# S3_Connectors.net
KiCad netlist of a schematic drawn in Altium Designer
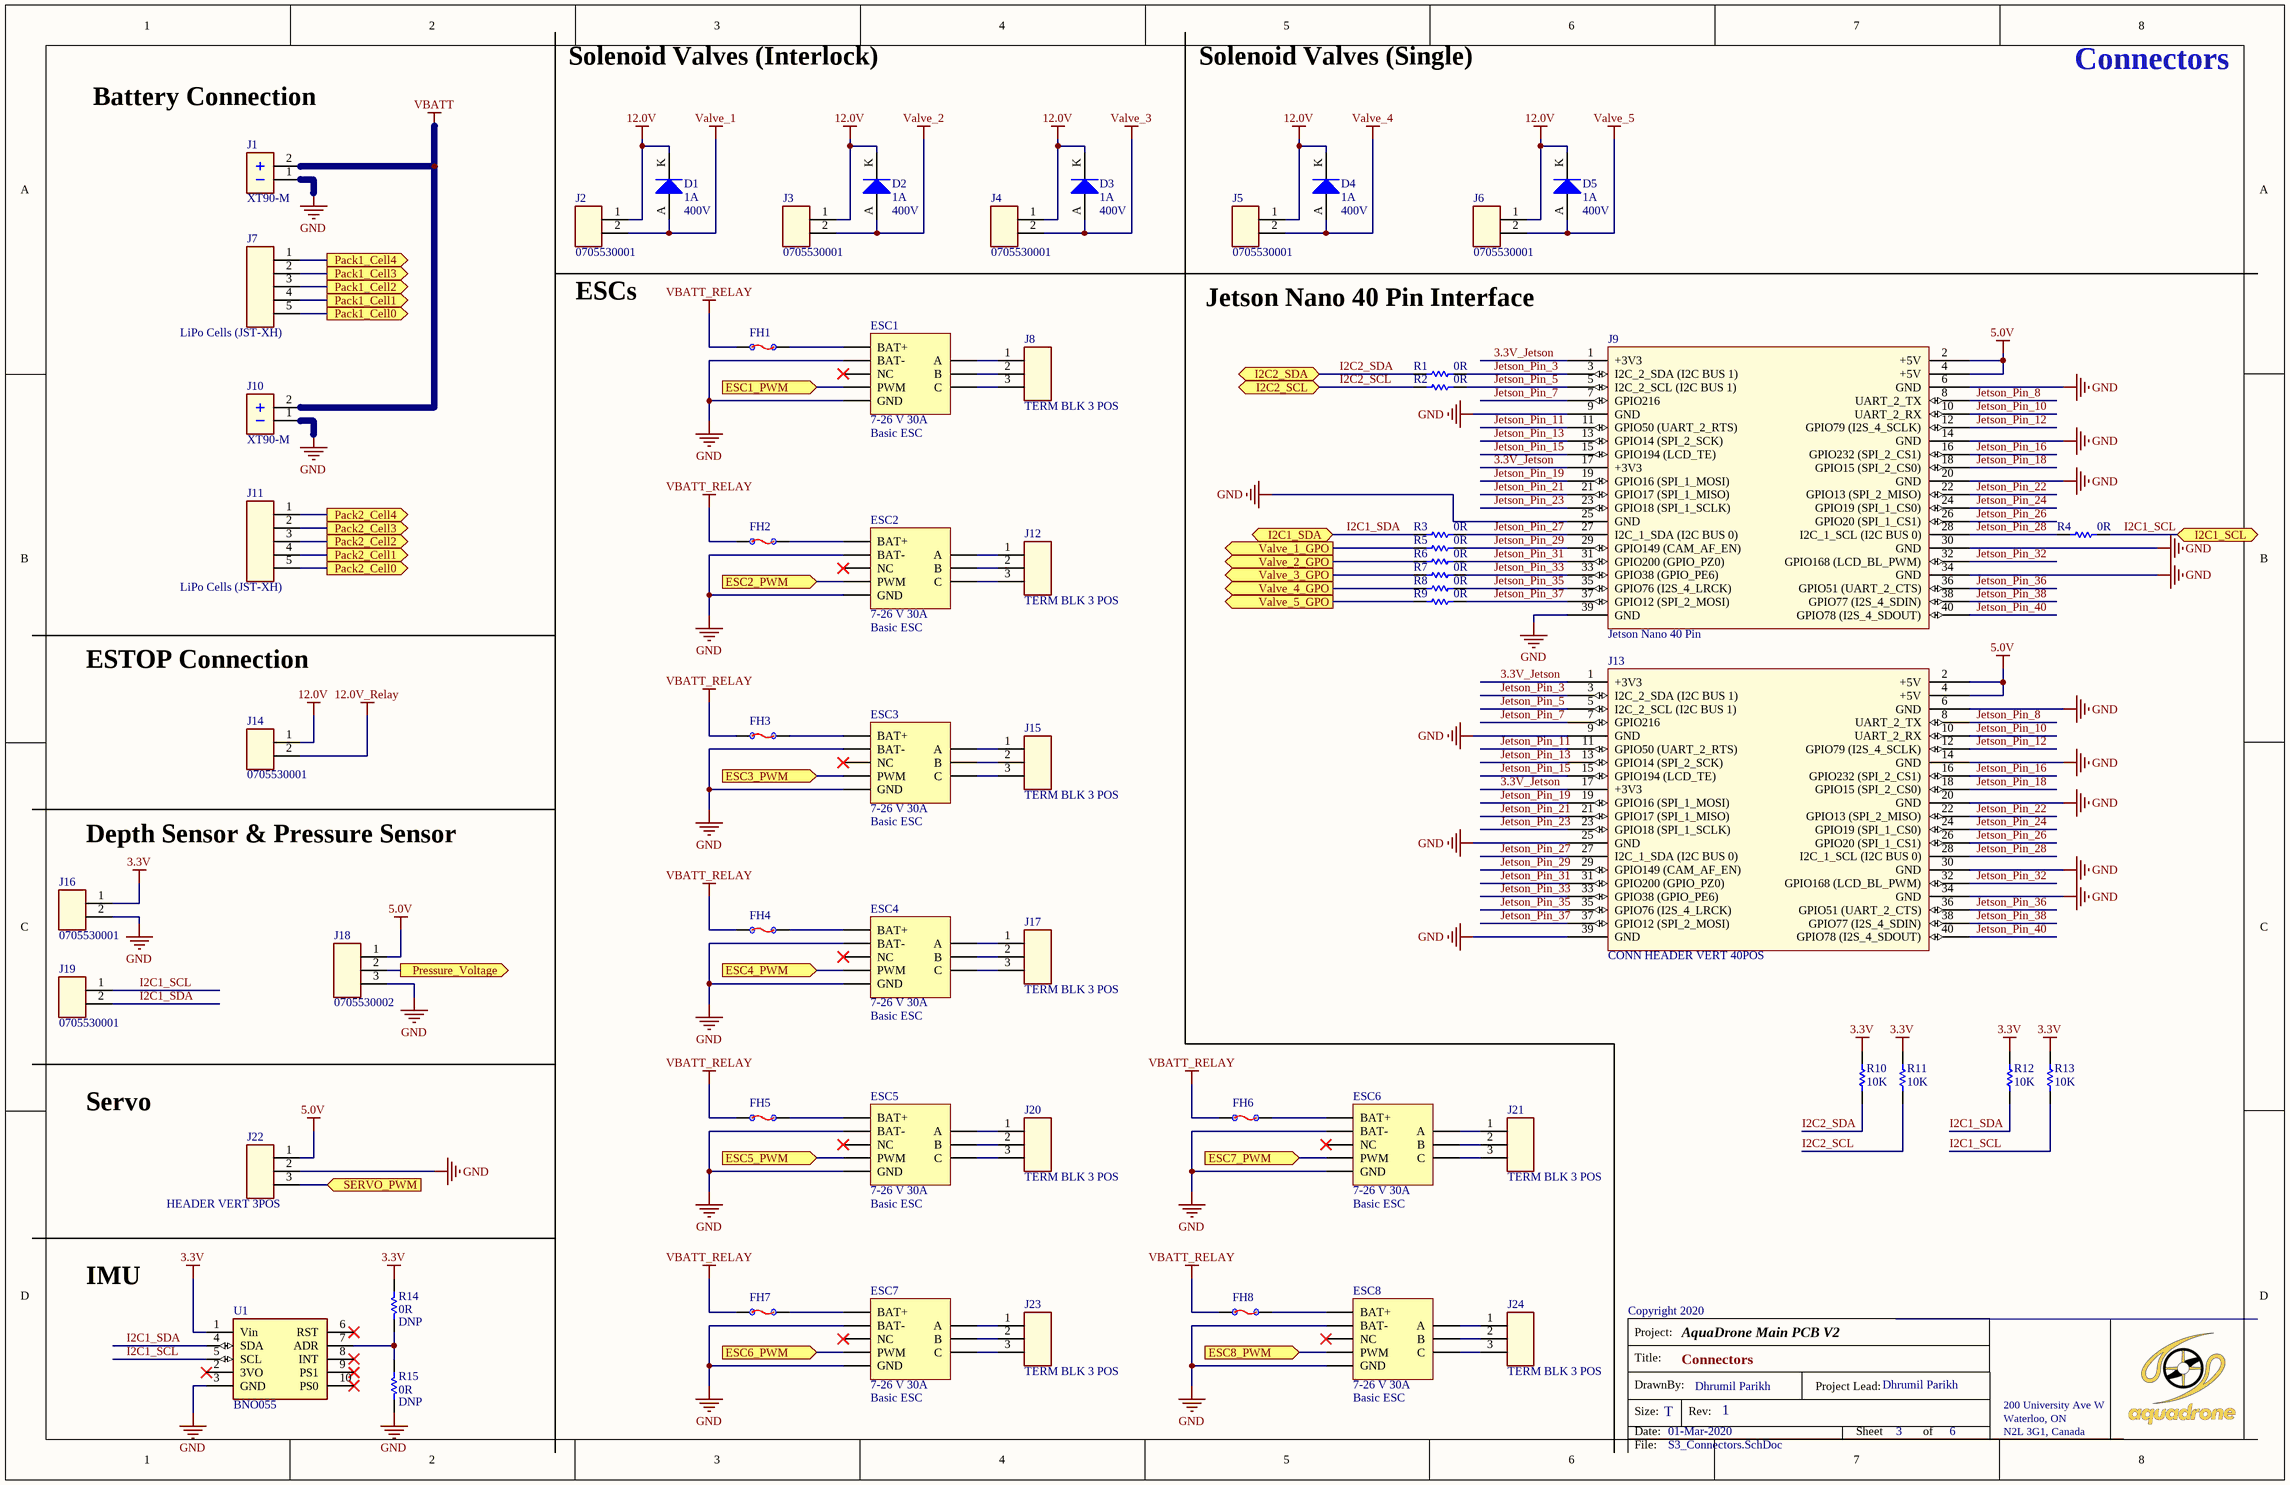
[diagram p0: S3_Connectors.SchDoc]

(export (version "E")
  (design (tool "Eeschema 10.0.6"))
  (components
    (comp (ref "D1")
      (value "DIODE GEN PURP 400V 1A SMA")
      (footprint "DIOM5226X295N")
      (fields
        (field (name "MFG") "SMC Diode Solutions")
        (field (name "MFG_PART_NO") "S1GTR")
        (field (name "CURRENT") "1A")
        (field (name "VR") "400V")
      )
      (libsource (lib "AquaDrone") (part "DIODE GEN PURP 400V 1A SMA"))
    )
    (comp (ref "D2")
      (value "DIODE GEN PURP 400V 1A SMA")
      (footprint "DIOM5226X295N")
      (fields
        (field (name "MFG") "SMC Diode Solutions")
        (field (name "MFG_PART_NO") "S1GTR")
        (field (name "CURRENT") "1A")
        (field (name "VR") "400V")
      )
      (libsource (lib "AquaDrone") (part "DIODE GEN PURP 400V 1A SMA"))
    )
    (comp (ref "D3")
      (value "DIODE GEN PURP 400V 1A SMA")
      (footprint "DIOM5226X295N")
      (fields
        (field (name "MFG") "SMC Diode Solutions")
        (field (name "MFG_PART_NO") "S1GTR")
        (field (name "CURRENT") "1A")
        (field (name "VR") "400V")
      )
      (libsource (lib "AquaDrone") (part "DIODE GEN PURP 400V 1A SMA"))
    )
    (comp (ref "D4")
      (value "DIODE GEN PURP 400V 1A SMA")
      (footprint "DIOM5226X295N")
      (fields
        (field (name "MFG") "SMC Diode Solutions")
        (field (name "MFG_PART_NO") "S1GTR")
        (field (name "CURRENT") "1A")
        (field (name "VR") "400V")
      )
      (libsource (lib "AquaDrone") (part "DIODE GEN PURP 400V 1A SMA"))
    )
    (comp (ref "D5")
      (value "DIODE GEN PURP 400V 1A SMA")
      (footprint "DIOM5226X295N")
      (fields
        (field (name "MFG") "SMC Diode Solutions")
        (field (name "MFG_PART_NO") "S1GTR")
        (field (name "CURRENT") "1A")
        (field (name "VR") "400V")
      )
      (libsource (lib "AquaDrone") (part "DIODE GEN PURP 400V 1A SMA"))
    )
    (comp (ref "ESC1")
      (value "Basic ESC")
      (footprint "ESC BR")
      (fields
        (field (name "MFG") "Blue Robotics")
        (field (name "MFG_PART_NO") "BESC30-R3")
        (field (name "VOLTAGE") "7-26 V 30A")
      )
      (libsource (lib "AquaDrone") (part "Basic ESC"))
    )
    (comp (ref "ESC2")
      (value "Basic ESC")
      (footprint "ESC BR")
      (fields
        (field (name "MFG") "Blue Robotics")
        (field (name "MFG_PART_NO") "BESC30-R3")
        (field (name "VOLTAGE") "7-26 V 30A")
      )
      (libsource (lib "AquaDrone") (part "Basic ESC"))
    )
    (comp (ref "ESC3")
      (value "Basic ESC")
      (footprint "ESC BR")
      (fields
        (field (name "MFG") "Blue Robotics")
        (field (name "MFG_PART_NO") "BESC30-R3")
        (field (name "VOLTAGE") "7-26 V 30A")
      )
      (libsource (lib "AquaDrone") (part "Basic ESC"))
    )
    (comp (ref "ESC4")
      (value "Basic ESC")
      (footprint "ESC BR")
      (fields
        (field (name "MFG") "Blue Robotics")
        (field (name "MFG_PART_NO") "BESC30-R3")
        (field (name "VOLTAGE") "7-26 V 30A")
      )
      (libsource (lib "AquaDrone") (part "Basic ESC"))
    )
    (comp (ref "ESC5")
      (value "Basic ESC")
      (footprint "ESC BR")
      (fields
        (field (name "MFG") "Blue Robotics")
        (field (name "MFG_PART_NO") "BESC30-R3")
        (field (name "VOLTAGE") "7-26 V 30A")
      )
      (libsource (lib "AquaDrone") (part "Basic ESC"))
    )
    (comp (ref "ESC6")
      (value "Basic ESC")
      (footprint "ESC BR")
      (fields
        (field (name "MFG") "Blue Robotics")
        (field (name "MFG_PART_NO") "BESC30-R3")
        (field (name "VOLTAGE") "7-26 V 30A")
      )
      (libsource (lib "AquaDrone") (part "Basic ESC"))
    )
    (comp (ref "ESC7")
      (value "Basic ESC")
      (footprint "ESC BR")
      (fields
        (field (name "MFG") "Blue Robotics")
        (field (name "MFG_PART_NO") "BESC30-R3")
        (field (name "VOLTAGE") "7-26 V 30A")
      )
      (libsource (lib "AquaDrone") (part "Basic ESC"))
    )
    (comp (ref "ESC8")
      (value "Basic ESC")
      (footprint "ESC BR")
      (fields
        (field (name "MFG") "Blue Robotics")
        (field (name "MFG_PART_NO") "BESC30-R3")
        (field (name "VOLTAGE") "7-26 V 30A")
      )
      (libsource (lib "AquaDrone") (part "Basic ESC"))
    )
    (comp (ref "FH1")
      (value "FUSE BLOK CARTRIDGE 600V 16A PCB")
      (footprint "FUSE-HOLDER(5X20)")
      (fields
        (field (name "MFG") "Schurter Inc.")
        (field (name "MFG_PART_NO") "0031.8231")
        (field (name "VOLTAGE") "600V")
      )
      (libsource (lib "AquaDrone") (part "FUSE BLOK CARTRIDGE 600V 16A PCB"))
    )
    (comp (ref "FH2")
      (value "FUSE BLOK CARTRIDGE 600V 16A PCB")
      (footprint "FUSE-HOLDER(5X20)")
      (fields
        (field (name "MFG") "Schurter Inc.")
        (field (name "MFG_PART_NO") "0031.8231")
        (field (name "VOLTAGE") "600V")
      )
      (libsource (lib "AquaDrone") (part "FUSE BLOK CARTRIDGE 600V 16A PCB"))
    )
    (comp (ref "FH3")
      (value "FUSE BLOK CARTRIDGE 600V 16A PCB")
      (footprint "FUSE-HOLDER(5X20)")
      (fields
        (field (name "MFG") "Schurter Inc.")
        (field (name "MFG_PART_NO") "0031.8231")
        (field (name "VOLTAGE") "600V")
      )
      (libsource (lib "AquaDrone") (part "FUSE BLOK CARTRIDGE 600V 16A PCB"))
    )
    (comp (ref "FH4")
      (value "FUSE BLOK CARTRIDGE 600V 16A PCB")
      (footprint "FUSE-HOLDER(5X20)")
      (fields
        (field (name "MFG") "Schurter Inc.")
        (field (name "MFG_PART_NO") "0031.8231")
        (field (name "VOLTAGE") "600V")
      )
      (libsource (lib "AquaDrone") (part "FUSE BLOK CARTRIDGE 600V 16A PCB"))
    )
    (comp (ref "FH5")
      (value "FUSE BLOK CARTRIDGE 600V 16A PCB")
      (footprint "FUSE-HOLDER(5X20)")
      (fields
        (field (name "MFG") "Schurter Inc.")
        (field (name "MFG_PART_NO") "0031.8231")
        (field (name "VOLTAGE") "600V")
      )
      (libsource (lib "AquaDrone") (part "FUSE BLOK CARTRIDGE 600V 16A PCB"))
    )
    (comp (ref "FH6")
      (value "FUSE BLOK CARTRIDGE 600V 16A PCB")
      (footprint "FUSE-HOLDER(5X20)")
      (fields
        (field (name "MFG") "Schurter Inc.")
        (field (name "MFG_PART_NO") "0031.8231")
        (field (name "VOLTAGE") "600V")
      )
      (libsource (lib "AquaDrone") (part "FUSE BLOK CARTRIDGE 600V 16A PCB"))
    )
    (comp (ref "FH7")
      (value "FUSE BLOK CARTRIDGE 600V 16A PCB")
      (footprint "FUSE-HOLDER(5X20)")
      (fields
        (field (name "MFG") "Schurter Inc.")
        (field (name "MFG_PART_NO") "0031.8231")
        (field (name "VOLTAGE") "600V")
      )
      (libsource (lib "AquaDrone") (part "FUSE BLOK CARTRIDGE 600V 16A PCB"))
    )
    (comp (ref "FH8")
      (value "FUSE BLOK CARTRIDGE 600V 16A PCB")
      (footprint "FUSE-HOLDER(5X20)")
      (fields
        (field (name "MFG") "Schurter Inc.")
        (field (name "MFG_PART_NO") "0031.8231")
        (field (name "VOLTAGE") "600V")
      )
      (libsource (lib "AquaDrone") (part "FUSE BLOK CARTRIDGE 600V 16A PCB"))
    )
    (comp (ref "J1")
      (value "XT90-M")
      (footprint "XT90")
      (description "CONN XT90 MALE")
      (fields (field (name "MFG") "DFRobot") (field (name "MFG_PART_NO") "FIT0588"))
      (libsource (lib "AquaDrone") (part "CONN XT90 MALE"))
    )
    (comp (ref "J2")
      (value "0705530001")
      (footprint "SHDRRA2W109P0_254_1X2_762X1359X699P")
      (description "CONN HEADER R/A 2POS 2.54MM")
      (fields (field (name "MFG") "Molex"))
      (libsource (lib "AquaDrone") (part "CONN HEADER R/A 2POS 2.54MM"))
    )
    (comp (ref "J3")
      (value "0705530001")
      (footprint "SHDRRA2W109P0_254_1X2_762X1359X699P")
      (description "CONN HEADER R/A 2POS 2.54MM")
      (fields (field (name "MFG") "Molex"))
      (libsource (lib "AquaDrone") (part "CONN HEADER R/A 2POS 2.54MM"))
    )
    (comp (ref "J4")
      (value "0705530001")
      (footprint "SHDRRA2W109P0_254_1X2_762X1359X699P")
      (description "CONN HEADER R/A 2POS 2.54MM")
      (fields (field (name "MFG") "Molex"))
      (libsource (lib "AquaDrone") (part "CONN HEADER R/A 2POS 2.54MM"))
    )
    (comp (ref "J5")
      (value "0705530001")
      (footprint "SHDRRA2W109P0_254_1X2_762X1359X699P")
      (description "CONN HEADER R/A 2POS 2.54MM")
      (fields (field (name "MFG") "Molex"))
      (libsource (lib "AquaDrone") (part "CONN HEADER R/A 2POS 2.54MM"))
    )
    (comp (ref "J6")
      (value "0705530001")
      (footprint "SHDRRA2W109P0_254_1X2_762X1359X699P")
      (description "CONN HEADER R/A 2POS 2.54MM")
      (fields (field (name "MFG") "Molex"))
      (libsource (lib "AquaDrone") (part "CONN HEADER R/A 2POS 2.54MM"))
    )
    (comp (ref "J7")
      (value "LiPo Cells (JST-XH)")
      (footprint "SHDR5W64P0X250_1X5_1490X1150X610P")
      (description "CONN HEADER R/A 5POS 2.5MM")
      (fields (field (name "MFG") "JST Sales America Inc.") (field (name "MFG_PART_NO") "S5B-XH-A(LF)(SN)"))
      (libsource (lib "AquaDrone") (part "CONN HEADER R/A 5POS 2.5MM"))
    )
    (comp (ref "J8")
      (value "TERM BLK 3 POS")
      (footprint "SHDR3W100P0X254_1X3_808X650X1030P")
      (description "TERM BLK 3P SIDE ENT 2.54MM PCB")
      (fields (field (name "MFG") "TE Connectivity") (field (name "MFG_PART_NO") "282834-3"))
      (libsource (lib "AquaDrone") (part "TERM BLK 3P SIDE ENT 2.54MM PCB"))
    )
    (comp (ref "J9")
      (value "Jetson Nano 40 Pin")
      (footprint "Jetson Nano")
      (description "Jetson Nano 40 Pin Interface")
      (fields (field (name "MFG") "Jetson") (field (name "MFG_PART_NO") "Nano"))
      (libsource (lib "AquaDrone") (part "Jetson Nano 40 Pin Interface"))
    )
    (comp (ref "J10")
      (value "XT90-M")
      (footprint "XT90")
      (description "CONN XT90 MALE")
      (fields (field (name "MFG") "DFRobot") (field (name "MFG_PART_NO") "FIT0588"))
      (libsource (lib "AquaDrone") (part "CONN XT90 MALE"))
    )
    (comp (ref "J11")
      (value "LiPo Cells (JST-XH)")
      (footprint "SHDR5W64P0X250_1X5_1490X1150X610P")
      (description "CONN HEADER R/A 5POS 2.5MM")
      (fields (field (name "MFG") "JST Sales America Inc.") (field (name "MFG_PART_NO") "S5B-XH-A(LF)(SN)"))
      (libsource (lib "AquaDrone") (part "CONN HEADER R/A 5POS 2.5MM"))
    )
    (comp (ref "J12")
      (value "TERM BLK 3 POS")
      (footprint "SHDR3W100P0X254_1X3_808X650X1030P")
      (description "TERM BLK 3P SIDE ENT 2.54MM PCB")
      (fields (field (name "MFG") "TE Connectivity") (field (name "MFG_PART_NO") "282834-3"))
      (libsource (lib "AquaDrone") (part "TERM BLK 3P SIDE ENT 2.54MM PCB"))
    )
    (comp (ref "J13")
      (value "CONN HEADER VERT 40POS")
      (footprint "67997-140HLF")
      (description "CONN HEADER VERT 40POS 2.54MM")
      (fields (field (name "MFG") "Amphenol") (field (name "MFG_PART_NO") "67997-140HLF"))
      (libsource (lib "AquaDrone") (part "CONN HEADER VERT 40POS 2.54MM"))
    )
    (comp (ref "J14")
      (value "0705530001")
      (footprint "SHDRRA2W109P0_254_1X2_762X1359X699P")
      (description "CONN HEADER R/A 2POS 2.54MM")
      (fields (field (name "MFG") "Molex"))
      (libsource (lib "AquaDrone") (part "CONN HEADER R/A 2POS 2.54MM"))
    )
    (comp (ref "J15")
      (value "TERM BLK 3 POS")
      (footprint "SHDR3W100P0X254_1X3_808X650X1030P")
      (description "TERM BLK 3P SIDE ENT 2.54MM PCB")
      (fields (field (name "MFG") "TE Connectivity") (field (name "MFG_PART_NO") "282834-3"))
      (libsource (lib "AquaDrone") (part "TERM BLK 3P SIDE ENT 2.54MM PCB"))
    )
    (comp (ref "J16")
      (value "0705530001")
      (footprint "SHDRRA2W109P0_254_1X2_762X1359X699P")
      (description "CONN HEADER R/A 2POS 2.54MM")
      (fields (field (name "MFG") "Molex"))
      (libsource (lib "AquaDrone") (part "CONN HEADER R/A 2POS 2.54MM"))
    )
    (comp (ref "J17")
      (value "TERM BLK 3 POS")
      (footprint "SHDR3W100P0X254_1X3_808X650X1030P")
      (description "TERM BLK 3P SIDE ENT 2.54MM PCB")
      (fields (field (name "MFG") "TE Connectivity") (field (name "MFG_PART_NO") "282834-3"))
      (libsource (lib "AquaDrone") (part "TERM BLK 3P SIDE ENT 2.54MM PCB"))
    )
    (comp (ref "J18")
      (value "0705530002")
      (footprint "SHDR3W89P0X254_1X3_1017X1359X699P")
      (description "CONN HEADER R/A 3POS 2.54MM")
      (fields (field (name "MFG") "Molex"))
      (libsource (lib "AquaDrone") (part "CONN HEADER R/A 3POS 2.54MM"))
    )
    (comp (ref "J19")
      (value "0705530001")
      (footprint "SHDRRA2W109P0_254_1X2_762X1359X699P")
      (description "CONN HEADER R/A 2POS 2.54MM")
      (fields (field (name "MFG") "Molex"))
      (libsource (lib "AquaDrone") (part "CONN HEADER R/A 2POS 2.54MM"))
    )
    (comp (ref "J20")
      (value "TERM BLK 3 POS")
      (footprint "SHDR3W100P0X254_1X3_808X650X1030P")
      (description "TERM BLK 3P SIDE ENT 2.54MM PCB")
      (fields (field (name "MFG") "TE Connectivity") (field (name "MFG_PART_NO") "282834-3"))
      (libsource (lib "AquaDrone") (part "TERM BLK 3P SIDE ENT 2.54MM PCB"))
    )
    (comp (ref "J21")
      (value "TERM BLK 3 POS")
      (footprint "SHDR3W100P0X254_1X3_808X650X1030P")
      (description "TERM BLK 3P SIDE ENT 2.54MM PCB")
      (fields (field (name "MFG") "TE Connectivity") (field (name "MFG_PART_NO") "282834-3"))
      (libsource (lib "AquaDrone") (part "TERM BLK 3P SIDE ENT 2.54MM PCB"))
    )
    (comp (ref "J22")
      (value "HEADER VERT 3POS")
      (footprint "RWMN:61300311121")
      (description "CONN HEADER VERT 3POS 2.54MM")
      (fields (field (name "MFG") "Wurth Electronics Inc.") (field (name "MFG_PART_NO") "61300311121"))
      (libsource (lib "AquaDrone") (part "CONN HEADER VERT 3POS 2.54MM"))
    )
    (comp (ref "J23")
      (value "TERM BLK 3 POS")
      (footprint "SHDR3W100P0X254_1X3_808X650X1030P")
      (description "TERM BLK 3P SIDE ENT 2.54MM PCB")
      (fields (field (name "MFG") "TE Connectivity") (field (name "MFG_PART_NO") "282834-3"))
      (libsource (lib "AquaDrone") (part "TERM BLK 3P SIDE ENT 2.54MM PCB"))
    )
    (comp (ref "J24")
      (value "TERM BLK 3 POS")
      (footprint "SHDR3W100P0X254_1X3_808X650X1030P")
      (description "TERM BLK 3P SIDE ENT 2.54MM PCB")
      (fields (field (name "MFG") "TE Connectivity") (field (name "MFG_PART_NO") "282834-3"))
      (libsource (lib "AquaDrone") (part "TERM BLK 3P SIDE ENT 2.54MM PCB"))
    )
    (comp (ref "R1")
      (value "0R")
      (footprint "RESC2012X07N")
      (description "RES SMD 0 OHM JUMPER 1/8W 0805")
      (fields (field (name "MFG") "Panasonic") (field (name "MFG_PART_NO") "ERJ-6GEY0R00V"))
      (libsource (lib "AquaDrone") (part "RES SMD 0 OHM JUMPER 1/8W 0805"))
    )
    (comp (ref "R2")
      (value "0R")
      (footprint "RESC2012X07N")
      (description "RES SMD 0 OHM JUMPER 1/8W 0805")
      (fields (field (name "MFG") "Panasonic") (field (name "MFG_PART_NO") "ERJ-6GEY0R00V"))
      (libsource (lib "AquaDrone") (part "RES SMD 0 OHM JUMPER 1/8W 0805"))
    )
    (comp (ref "R3")
      (value "0R")
      (footprint "RESC2012X07N")
      (description "RES SMD 0 OHM JUMPER 1/8W 0805")
      (fields (field (name "MFG") "Panasonic") (field (name "MFG_PART_NO") "ERJ-6GEY0R00V"))
      (libsource (lib "AquaDrone") (part "RES SMD 0 OHM JUMPER 1/8W 0805"))
    )
    (comp (ref "R4")
      (value "0R")
      (footprint "RESC2012X07N")
      (description "RES SMD 0 OHM JUMPER 1/8W 0805")
      (fields (field (name "MFG") "Panasonic") (field (name "MFG_PART_NO") "ERJ-6GEY0R00V"))
      (libsource (lib "AquaDrone") (part "RES SMD 0 OHM JUMPER 1/8W 0805"))
    )
    (comp (ref "R5")
      (value "0R")
      (footprint "RESC2012X07N")
      (description "RES SMD 0 OHM JUMPER 1/8W 0805")
      (fields (field (name "MFG") "Panasonic") (field (name "MFG_PART_NO") "ERJ-6GEY0R00V"))
      (libsource (lib "AquaDrone") (part "RES SMD 0 OHM JUMPER 1/8W 0805"))
    )
    (comp (ref "R6")
      (value "0R")
      (footprint "RESC2012X07N")
      (description "RES SMD 0 OHM JUMPER 1/8W 0805")
      (fields (field (name "MFG") "Panasonic") (field (name "MFG_PART_NO") "ERJ-6GEY0R00V"))
      (libsource (lib "AquaDrone") (part "RES SMD 0 OHM JUMPER 1/8W 0805"))
    )
    (comp (ref "R7")
      (value "0R")
      (footprint "RESC2012X07N")
      (description "RES SMD 0 OHM JUMPER 1/8W 0805")
      (fields (field (name "MFG") "Panasonic") (field (name "MFG_PART_NO") "ERJ-6GEY0R00V"))
      (libsource (lib "AquaDrone") (part "RES SMD 0 OHM JUMPER 1/8W 0805"))
    )
    (comp (ref "R8")
      (value "0R")
      (footprint "RESC2012X07N")
      (description "RES SMD 0 OHM JUMPER 1/8W 0805")
      (fields (field (name "MFG") "Panasonic") (field (name "MFG_PART_NO") "ERJ-6GEY0R00V"))
      (libsource (lib "AquaDrone") (part "RES SMD 0 OHM JUMPER 1/8W 0805"))
    )
    (comp (ref "R9")
      (value "0R")
      (footprint "RESC2012X07N")
      (description "RES SMD 0 OHM JUMPER 1/8W 0805")
      (fields (field (name "MFG") "Panasonic") (field (name "MFG_PART_NO") "ERJ-6GEY0R00V"))
      (libsource (lib "AquaDrone") (part "RES SMD 0 OHM JUMPER 1/8W 0805"))
    )
    (comp (ref "R10")
      (value "10K")
      (footprint "RESC1608X06N")
      (description "RES SMD 10K OHM 1% 1/10W 0603")
      (fields (field (name "MFG") "Vishay Dale") (field (name "MFG_PART_NO") "CRCW060310K0FKEA"))
      (libsource (lib "AquaDrone") (part "RES SMD 10K OHM 1% 1/10W 0603"))
    )
    (comp (ref "R11")
      (value "10K")
      (footprint "RESC1608X06N")
      (description "RES SMD 10K OHM 1% 1/10W 0603")
      (fields (field (name "MFG") "Vishay Dale") (field (name "MFG_PART_NO") "CRCW060310K0FKEA"))
      (libsource (lib "AquaDrone") (part "RES SMD 10K OHM 1% 1/10W 0603"))
    )
    (comp (ref "R12")
      (value "10K")
      (footprint "RESC1608X06N")
      (description "RES SMD 10K OHM 1% 1/10W 0603")
      (fields (field (name "MFG") "Vishay Dale") (field (name "MFG_PART_NO") "CRCW060310K0FKEA"))
      (libsource (lib "AquaDrone") (part "RES SMD 10K OHM 1% 1/10W 0603"))
    )
    (comp (ref "R13")
      (value "10K")
      (footprint "RESC1608X06N")
      (description "RES SMD 10K OHM 1% 1/10W 0603")
      (fields (field (name "MFG") "Vishay Dale") (field (name "MFG_PART_NO") "CRCW060310K0FKEA"))
      (libsource (lib "AquaDrone") (part "RES SMD 10K OHM 1% 1/10W 0603"))
    )
    (comp (ref "R14")
      (value "0R")
      (footprint "RESC2012X07N")
      (description "RES SMD 0 OHM JUMPER 1/8W 0805")
      (fields
        (field (name "MFG") "Panasonic")
        (field (name "NOSTUFF") "DNP")
        (field (name "MFG_PART_NO") "ERJ-6GEY0R00V")
      )
      (libsource (lib "AquaDrone") (part "RES SMD 0 OHM JUMPER 1/8W 0805"))
    )
    (comp (ref "R15")
      (value "0R")
      (footprint "RESC2012X07N")
      (description "RES SMD 0 OHM JUMPER 1/8W 0805")
      (fields
        (field (name "MFG") "Panasonic")
        (field (name "NOSTUFF") "DNP")
        (field (name "MFG_PART_NO") "ERJ-6GEY0R00V")
      )
      (libsource (lib "AquaDrone") (part "RES SMD 0 OHM JUMPER 1/8W 0805"))
    )
    (comp (ref "U1")
      (value "IC BNO055")
      (footprint "BNO055")
      (fields (field (name "MFG") "Adafruit Industries LLC") (field (name "MFG_PART_NO") "BNO055"))
      (libsource (lib "AquaDrone") (part "IC BNO055"))
    )
  )
  (nets
    (net (code "1") (name "/3.3V_Jetson") (class "Default")
      (node (ref "J13") (pin "1") (pinfunction "+3V3_1") (pintype "power_in"))
      (node (ref "J13") (pin "17") (pinfunction "+3V3_17") (pintype "power_in"))
      (node (ref "J9") (pin "1") (pinfunction "+3V3_1") (pintype "power_in"))
      (node (ref "J9") (pin "17") (pinfunction "+3V3_17") (pintype "power_in"))
    )
    (net (code "2") (name "/ESC1_PWM") (class "Default")
      (node (ref "ESC1") (pin "PWM") (pinfunction "PWM_PWM") (pintype "passive"))
    )
    (net (code "3") (name "/ESC2_PWM") (class "Default")
      (node (ref "ESC2") (pin "PWM") (pinfunction "PWM_PWM") (pintype "passive"))
    )
    (net (code "4") (name "/ESC3_PWM") (class "Default")
      (node (ref "ESC3") (pin "PWM") (pinfunction "PWM_PWM") (pintype "passive"))
    )
    (net (code "5") (name "/ESC4_PWM") (class "Default")
      (node (ref "ESC4") (pin "PWM") (pinfunction "PWM_PWM") (pintype "passive"))
    )
    (net (code "6") (name "/ESC5_PWM") (class "Default")
      (node (ref "ESC5") (pin "PWM") (pinfunction "PWM_PWM") (pintype "passive"))
    )
    (net (code "7") (name "/ESC6_PWM") (class "Default")
      (node (ref "ESC7") (pin "PWM") (pinfunction "PWM_PWM") (pintype "passive"))
    )
    (net (code "8") (name "/ESC7_PWM") (class "Default")
      (node (ref "ESC6") (pin "PWM") (pinfunction "PWM_PWM") (pintype "passive"))
    )
    (net (code "9") (name "/ESC8_PWM") (class "Default")
      (node (ref "ESC8") (pin "PWM") (pinfunction "PWM_PWM") (pintype "passive"))
    )
    (net (code "10") (name "/I2C1_SCL") (class "Default")
      (node (ref "J19") (pin "1") (pintype "passive"))
      (node (ref "R13") (pin "1") (pinfunction "1_1") (pintype "passive"))
      (node (ref "R4") (pin "2") (pinfunction "2_2") (pintype "passive"))
      (node (ref "U1") (pin "5") (pinfunction "SCL_5") (pintype "bidirectional"))
    )
    (net (code "11") (name "/I2C1_SDA") (class "Default")
      (node (ref "J19") (pin "2") (pintype "passive"))
      (node (ref "R12") (pin "1") (pinfunction "1_1") (pintype "passive"))
      (node (ref "R3") (pin "1") (pinfunction "1_1") (pintype "passive"))
      (node (ref "U1") (pin "4") (pinfunction "SDA_4") (pintype "bidirectional"))
    )
    (net (code "12") (name "/I2C2_SCL") (class "Default")
      (node (ref "R11") (pin "1") (pinfunction "1_1") (pintype "passive"))
      (node (ref "R2") (pin "1") (pinfunction "1_1") (pintype "passive"))
    )
    (net (code "13") (name "/I2C2_SDA") (class "Default")
      (node (ref "R1") (pin "1") (pinfunction "1_1") (pintype "passive"))
      (node (ref "R10") (pin "1") (pinfunction "1_1") (pintype "passive"))
    )
    (net (code "14") (name "/Jetson_Pin_3") (class "Default")
      (node (ref "J13") (pin "3") (pinfunction "I2C_2_SDA_(I2C_BUS_1)_3") (pintype "bidirectional"))
      (node (ref "J9") (pin "3") (pinfunction "I2C_2_SDA_(I2C_BUS_1)_3") (pintype "bidirectional"))
      (node (ref "R1") (pin "2") (pinfunction "2_2") (pintype "passive"))
    )
    (net (code "15") (name "/Jetson_Pin_5") (class "Default")
      (node (ref "J13") (pin "5") (pinfunction "I2C_2_SCL_(I2C_BUS_1)_5") (pintype "bidirectional"))
      (node (ref "J9") (pin "5") (pinfunction "I2C_2_SCL_(I2C_BUS_1)_5") (pintype "bidirectional"))
      (node (ref "R2") (pin "2") (pinfunction "2_2") (pintype "passive"))
    )
    (net (code "16") (name "/Jetson_Pin_7") (class "Default")
      (node (ref "J13") (pin "7") (pinfunction "GPIO216_7") (pintype "bidirectional"))
      (node (ref "J9") (pin "7") (pinfunction "GPIO216_7") (pintype "bidirectional"))
    )
    (net (code "17") (name "/Jetson_Pin_8") (class "Default")
      (node (ref "J13") (pin "8") (pinfunction "UART_2_TX_8") (pintype "bidirectional"))
      (node (ref "J9") (pin "8") (pinfunction "UART_2_TX_8") (pintype "bidirectional"))
    )
    (net (code "18") (name "/Jetson_Pin_10") (class "Default")
      (node (ref "J13") (pin "10") (pinfunction "UART_2_RX_10") (pintype "bidirectional"))
      (node (ref "J9") (pin "10") (pinfunction "UART_2_RX_10") (pintype "bidirectional"))
    )
    (net (code "19") (name "/Jetson_Pin_11") (class "Default")
      (node (ref "J13") (pin "11") (pinfunction "GPIO50_(UART_2_RTS)_11") (pintype "bidirectional"))
      (node (ref "J9") (pin "11") (pinfunction "GPIO50_(UART_2_RTS)_11") (pintype "bidirectional"))
    )
    (net (code "20") (name "/Jetson_Pin_12") (class "Default")
      (node (ref "J13") (pin "12") (pinfunction "GPIO79_(I2S_4_SCLK)_12") (pintype "bidirectional"))
      (node (ref "J9") (pin "12") (pinfunction "GPIO79_(I2S_4_SCLK)_12") (pintype "bidirectional"))
    )
    (net (code "21") (name "/Jetson_Pin_13") (class "Default")
      (node (ref "J13") (pin "13") (pinfunction "GPIO14_(SPI_2_SCK)_13") (pintype "bidirectional"))
      (node (ref "J9") (pin "13") (pinfunction "GPIO14_(SPI_2_SCK)_13") (pintype "bidirectional"))
    )
    (net (code "22") (name "/Jetson_Pin_15") (class "Default")
      (node (ref "J13") (pin "15") (pinfunction "GPIO194_(LCD_TE)_15") (pintype "bidirectional"))
      (node (ref "J9") (pin "15") (pinfunction "GPIO194_(LCD_TE)_15") (pintype "bidirectional"))
    )
    (net (code "23") (name "/Jetson_Pin_16") (class "Default")
      (node (ref "J13") (pin "16") (pinfunction "GPIO232_(SPI_2_CS1)_16") (pintype "bidirectional"))
      (node (ref "J9") (pin "16") (pinfunction "GPIO232_(SPI_2_CS1)_16") (pintype "bidirectional"))
    )
    (net (code "24") (name "/Jetson_Pin_18") (class "Default")
      (node (ref "J13") (pin "18") (pinfunction "GPIO15_(SPI_2_CS0)_18") (pintype "bidirectional"))
      (node (ref "J9") (pin "18") (pinfunction "GPIO15_(SPI_2_CS0)_18") (pintype "bidirectional"))
    )
    (net (code "25") (name "/Jetson_Pin_19") (class "Default")
      (node (ref "J13") (pin "19") (pinfunction "GPIO16_(SPI_1_MOSI)_19") (pintype "bidirectional"))
      (node (ref "J9") (pin "19") (pinfunction "GPIO16_(SPI_1_MOSI)_19") (pintype "bidirectional"))
    )
    (net (code "26") (name "/Jetson_Pin_21") (class "Default")
      (node (ref "J13") (pin "21") (pinfunction "GPIO17_(SPI_1_MISO)_21") (pintype "bidirectional"))
      (node (ref "J9") (pin "21") (pinfunction "GPIO17_(SPI_1_MISO)_21") (pintype "bidirectional"))
    )
    (net (code "27") (name "/Jetson_Pin_22") (class "Default")
      (node (ref "J13") (pin "22") (pinfunction "GPIO13_(SPI_2_MISO)_22") (pintype "bidirectional"))
      (node (ref "J9") (pin "22") (pinfunction "GPIO13_(SPI_2_MISO)_22") (pintype "bidirectional"))
    )
    (net (code "28") (name "/Jetson_Pin_23") (class "Default")
      (node (ref "J13") (pin "23") (pinfunction "GPIO18_(SPI_1_SCLK)_23") (pintype "bidirectional"))
      (node (ref "J9") (pin "23") (pinfunction "GPIO18_(SPI_1_SCLK)_23") (pintype "bidirectional"))
    )
    (net (code "29") (name "/Jetson_Pin_24") (class "Default")
      (node (ref "J13") (pin "24") (pinfunction "GPIO19_(SPI_1_CS0)_24") (pintype "bidirectional"))
      (node (ref "J9") (pin "24") (pinfunction "GPIO19_(SPI_1_CS0)_24") (pintype "bidirectional"))
    )
    (net (code "30") (name "/Jetson_Pin_26") (class "Default")
      (node (ref "J13") (pin "26") (pinfunction "GPIO20_(SPI_1_CS1)_26") (pintype "bidirectional"))
      (node (ref "J9") (pin "26") (pinfunction "GPIO20_(SPI_1_CS1)_26") (pintype "bidirectional"))
    )
    (net (code "31") (name "/Jetson_Pin_27") (class "Default")
      (node (ref "J13") (pin "27") (pinfunction "I2C_1_SDA_(I2C_BUS_0)_27") (pintype "passive"))
      (node (ref "J9") (pin "27") (pinfunction "I2C_1_SDA_(I2C_BUS_0)_27") (pintype "passive"))
      (node (ref "R3") (pin "2") (pinfunction "2_2") (pintype "passive"))
    )
    (net (code "32") (name "/Jetson_Pin_28") (class "Default")
      (node (ref "J13") (pin "28") (pinfunction "I2C_1_SCL_(I2C_BUS_0)_28") (pintype "passive"))
      (node (ref "J9") (pin "28") (pinfunction "I2C_1_SCL_(I2C_BUS_0)_28") (pintype "passive"))
      (node (ref "R4") (pin "1") (pinfunction "1_1") (pintype "passive"))
    )
    (net (code "33") (name "/Jetson_Pin_29") (class "Default")
      (node (ref "J13") (pin "29") (pinfunction "GPIO149_(CAM_AF_EN)_29") (pintype "bidirectional"))
      (node (ref "J9") (pin "29") (pinfunction "GPIO149_(CAM_AF_EN)_29") (pintype "bidirectional"))
      (node (ref "R5") (pin "2") (pinfunction "2_2") (pintype "passive"))
    )
    (net (code "34") (name "/Jetson_Pin_31") (class "Default")
      (node (ref "J13") (pin "31") (pinfunction "GPIO200_(GPIO_PZ0)_31") (pintype "bidirectional"))
      (node (ref "J9") (pin "31") (pinfunction "GPIO200_(GPIO_PZ0)_31") (pintype "bidirectional"))
      (node (ref "R6") (pin "2") (pinfunction "2_2") (pintype "passive"))
    )
    (net (code "35") (name "/Jetson_Pin_32") (class "Default")
      (node (ref "J13") (pin "32") (pinfunction "GPIO168_(LCD_BL_PWM)_32") (pintype "bidirectional"))
      (node (ref "J9") (pin "32") (pinfunction "GPIO168_(LCD_BL_PWM)_32") (pintype "bidirectional"))
    )
    (net (code "36") (name "/Jetson_Pin_33") (class "Default")
      (node (ref "J13") (pin "33") (pinfunction "GPIO38_(GPIO_PE6)_33") (pintype "bidirectional"))
      (node (ref "J9") (pin "33") (pinfunction "GPIO38_(GPIO_PE6)_33") (pintype "bidirectional"))
      (node (ref "R7") (pin "2") (pinfunction "2_2") (pintype "passive"))
    )
    (net (code "37") (name "/Jetson_Pin_35") (class "Default")
      (node (ref "J13") (pin "35") (pinfunction "GPIO76_(I2S_4_LRCK)_35") (pintype "bidirectional"))
      (node (ref "J9") (pin "35") (pinfunction "GPIO76_(I2S_4_LRCK)_35") (pintype "bidirectional"))
      (node (ref "R8") (pin "2") (pinfunction "2_2") (pintype "passive"))
    )
    (net (code "38") (name "/Jetson_Pin_36") (class "Default")
      (node (ref "J13") (pin "36") (pinfunction "GPIO51_(UART_2_CTS)_36") (pintype "bidirectional"))
      (node (ref "J9") (pin "36") (pinfunction "GPIO51_(UART_2_CTS)_36") (pintype "bidirectional"))
    )
    (net (code "39") (name "/Jetson_Pin_37") (class "Default")
      (node (ref "J13") (pin "37") (pinfunction "GPIO12_(SPI_2_MOSI)_37") (pintype "bidirectional"))
      (node (ref "J9") (pin "37") (pinfunction "GPIO12_(SPI_2_MOSI)_37") (pintype "bidirectional"))
      (node (ref "R9") (pin "2") (pinfunction "2_2") (pintype "passive"))
    )
    (net (code "40") (name "/Jetson_Pin_38") (class "Default")
      (node (ref "J13") (pin "38") (pinfunction "GPIO77_(I2S_4_SDIN)_38") (pintype "bidirectional"))
      (node (ref "J9") (pin "38") (pinfunction "GPIO77_(I2S_4_SDIN)_38") (pintype "bidirectional"))
    )
    (net (code "41") (name "/Jetson_Pin_40") (class "Default")
      (node (ref "J13") (pin "40") (pinfunction "GPIO78_(I2S_4_SDOUT)_40") (pintype "bidirectional"))
      (node (ref "J9") (pin "40") (pinfunction "GPIO78_(I2S_4_SDOUT)_40") (pintype "bidirectional"))
    )
    (net (code "42") (name "/Pack1_Cell0") (class "Default") (node (ref "J7") (pin "5") (pintype "passive")))
    (net (code "43") (name "/Pack1_Cell1") (class "Default") (node (ref "J7") (pin "4") (pintype "passive")))
    (net (code "44") (name "/Pack1_Cell2") (class "Default") (node (ref "J7") (pin "3") (pintype "passive")))
    (net (code "45") (name "/Pack1_Cell3") (class "Default") (node (ref "J7") (pin "2") (pintype "passive")))
    (net (code "46") (name "/Pack1_Cell4") (class "Default") (node (ref "J7") (pin "1") (pintype "passive")))
    (net (code "47") (name "/Pack2_Cell0") (class "Default") (node (ref "J11") (pin "5") (pintype "passive")))
    (net (code "48") (name "/Pack2_Cell1") (class "Default") (node (ref "J11") (pin "4") (pintype "passive")))
    (net (code "49") (name "/Pack2_Cell2") (class "Default") (node (ref "J11") (pin "3") (pintype "passive")))
    (net (code "50") (name "/Pack2_Cell3") (class "Default") (node (ref "J11") (pin "2") (pintype "passive")))
    (net (code "51") (name "/Pack2_Cell4") (class "Default") (node (ref "J11") (pin "1") (pintype "passive")))
    (net (code "52") (name "/Pressure_Voltage") (class "Default")
      (node (ref "J18") (pin "2") (pintype "passive"))
    )
    (net (code "53") (name "/SERVO_PWM") (class "Default") (node (ref "J22") (pin "3") (pintype "passive")))
    (net (code "54") (name "/Valve_1_GPO") (class "Default")
      (node (ref "R5") (pin "1") (pinfunction "1_1") (pintype "passive"))
    )
    (net (code "55") (name "/Valve_2_GPO") (class "Default")
      (node (ref "R6") (pin "1") (pinfunction "1_1") (pintype "passive"))
    )
    (net (code "56") (name "/Valve_3_GPO") (class "Default")
      (node (ref "R7") (pin "1") (pinfunction "1_1") (pintype "passive"))
    )
    (net (code "57") (name "/Valve_4_GPO") (class "Default")
      (node (ref "R8") (pin "1") (pinfunction "1_1") (pintype "passive"))
    )
    (net (code "58") (name "/Valve_5_GPO") (class "Default")
      (node (ref "R9") (pin "1") (pinfunction "1_1") (pintype "passive"))
    )
    (net (code "59") (name "3.3V") (class "Default")
      (node (ref "J16") (pin "1") (pintype "passive"))
      (node (ref "R10") (pin "2") (pinfunction "2_2") (pintype "passive"))
      (node (ref "R11") (pin "2") (pinfunction "2_2") (pintype "passive"))
      (node (ref "R12") (pin "2") (pinfunction "2_2") (pintype "passive"))
      (node (ref "R13") (pin "2") (pinfunction "2_2") (pintype "passive"))
      (node (ref "R14") (pin "1") (pinfunction "1_1") (pintype "passive"))
      (node (ref "U1") (pin "1") (pinfunction "Vin_1") (pintype "passive"))
    )
    (net (code "60") (name "5.0V") (class "Default")
      (node (ref "J13") (pin "2") (pinfunction "+5V_2") (pintype "power_in"))
      (node (ref "J13") (pin "4") (pinfunction "+5V_4") (pintype "power_in"))
      (node (ref "J18") (pin "1") (pintype "passive"))
      (node (ref "J22") (pin "1") (pintype "passive"))
      (node (ref "J9") (pin "2") (pinfunction "+5V_2") (pintype "power_in"))
      (node (ref "J9") (pin "4") (pinfunction "+5V_4") (pintype "power_in"))
    )
    (net (code "61") (name "12.0V") (class "Default")
      (node (ref "D1") (pin "K") (pinfunction "K_K") (pintype "passive"))
      (node (ref "D2") (pin "K") (pinfunction "K_K") (pintype "passive"))
      (node (ref "D3") (pin "K") (pinfunction "K_K") (pintype "passive"))
      (node (ref "D4") (pin "K") (pinfunction "K_K") (pintype "passive"))
      (node (ref "D5") (pin "K") (pinfunction "K_K") (pintype "passive"))
      (node (ref "J14") (pin "1") (pintype "passive"))
      (node (ref "J2") (pin "1") (pintype "passive"))
      (node (ref "J3") (pin "1") (pintype "passive"))
      (node (ref "J4") (pin "1") (pintype "passive"))
      (node (ref "J5") (pin "1") (pintype "passive"))
      (node (ref "J6") (pin "1") (pintype "passive"))
    )
    (net (code "62") (name "12.0V_Relay") (class "Default") (node (ref "J14") (pin "2") (pintype "passive")))
    (net (code "63") (name "GND") (class "Default")
      (node (ref "ESC1") (pin "BAT-") (pinfunction "BAT-_BAT-") (pintype "passive"))
      (node (ref "ESC1") (pin "GND") (pinfunction "GND_GND") (pintype "passive"))
      (node (ref "ESC2") (pin "BAT-") (pinfunction "BAT-_BAT-") (pintype "passive"))
      (node (ref "ESC2") (pin "GND") (pinfunction "GND_GND") (pintype "passive"))
      (node (ref "ESC3") (pin "BAT-") (pinfunction "BAT-_BAT-") (pintype "passive"))
      (node (ref "ESC3") (pin "GND") (pinfunction "GND_GND") (pintype "passive"))
      (node (ref "ESC4") (pin "BAT-") (pinfunction "BAT-_BAT-") (pintype "passive"))
      (node (ref "ESC4") (pin "GND") (pinfunction "GND_GND") (pintype "passive"))
      (node (ref "ESC5") (pin "BAT-") (pinfunction "BAT-_BAT-") (pintype "passive"))
      (node (ref "ESC5") (pin "GND") (pinfunction "GND_GND") (pintype "passive"))
      (node (ref "ESC6") (pin "BAT-") (pinfunction "BAT-_BAT-") (pintype "passive"))
      (node (ref "ESC6") (pin "GND") (pinfunction "GND_GND") (pintype "passive"))
      (node (ref "ESC7") (pin "BAT-") (pinfunction "BAT-_BAT-") (pintype "passive"))
      (node (ref "ESC7") (pin "GND") (pinfunction "GND_GND") (pintype "passive"))
      (node (ref "ESC8") (pin "BAT-") (pinfunction "BAT-_BAT-") (pintype "passive"))
      (node (ref "ESC8") (pin "GND") (pinfunction "GND_GND") (pintype "passive"))
      (node (ref "J1") (pin "1") (pintype "passive"))
      (node (ref "J10") (pin "1") (pintype "passive"))
      (node (ref "J13") (pin "14") (pinfunction "GND_14") (pintype "power_in"))
      (node (ref "J13") (pin "20") (pinfunction "GND_20") (pintype "power_in"))
      (node (ref "J13") (pin "25") (pinfunction "GND_25") (pintype "power_in"))
      (node (ref "J13") (pin "30") (pinfunction "GND_30") (pintype "power_in"))
      (node (ref "J13") (pin "34") (pinfunction "GND_34") (pintype "passive"))
      (node (ref "J13") (pin "39") (pinfunction "GND_39") (pintype "power_in"))
      (node (ref "J13") (pin "6") (pinfunction "GND_6") (pintype "power_in"))
      (node (ref "J13") (pin "9") (pinfunction "GND_9") (pintype "power_in"))
      (node (ref "J16") (pin "2") (pintype "passive"))
      (node (ref "J18") (pin "3") (pintype "passive"))
      (node (ref "J22") (pin "2") (pintype "passive"))
      (node (ref "J9") (pin "14") (pinfunction "GND_14") (pintype "power_in"))
      (node (ref "J9") (pin "20") (pinfunction "GND_20") (pintype "power_in"))
      (node (ref "J9") (pin "25") (pinfunction "GND_25") (pintype "power_in"))
      (node (ref "J9") (pin "30") (pinfunction "GND_30") (pintype "power_in"))
      (node (ref "J9") (pin "34") (pinfunction "GND_34") (pintype "passive"))
      (node (ref "J9") (pin "39") (pinfunction "GND_39") (pintype "power_in"))
      (node (ref "J9") (pin "6") (pinfunction "GND_6") (pintype "power_in"))
      (node (ref "J9") (pin "9") (pinfunction "GND_9") (pintype "power_in"))
      (node (ref "R15") (pin "2") (pinfunction "2_2") (pintype "passive"))
      (node (ref "U1") (pin "3") (pinfunction "GND_3") (pintype "passive"))
    )
    (net (code "64") (name "Net-(ESC1-PadA)") (class "Default")
      (node (ref "ESC1") (pin "A") (pinfunction "A_A") (pintype "passive"))
      (node (ref "J8") (pin "1") (pintype "passive"))
    )
    (net (code "65") (name "Net-(ESC1-PadB)") (class "Default")
      (node (ref "ESC1") (pin "B") (pinfunction "B_B") (pintype "passive"))
      (node (ref "J8") (pin "2") (pintype "passive"))
    )
    (net (code "66") (name "Net-(ESC1-PadBAT+)") (class "Default")
      (node (ref "ESC1") (pin "BAT+") (pinfunction "BAT+_BAT+") (pintype "passive"))
      (node (ref "FH1") (pin "2") (pinfunction "2_2") (pintype "passive"))
    )
    (net (code "67") (name "Net-(ESC1-PadC)") (class "Default")
      (node (ref "ESC1") (pin "C") (pinfunction "C_C") (pintype "passive"))
      (node (ref "J8") (pin "3") (pintype "passive"))
    )
    (net (code "68") (name "Net-(ESC2-PadA)") (class "Default")
      (node (ref "ESC2") (pin "A") (pinfunction "A_A") (pintype "passive"))
      (node (ref "J12") (pin "1") (pintype "passive"))
    )
    (net (code "69") (name "Net-(ESC2-PadB)") (class "Default")
      (node (ref "ESC2") (pin "B") (pinfunction "B_B") (pintype "passive"))
      (node (ref "J12") (pin "2") (pintype "passive"))
    )
    (net (code "70") (name "Net-(ESC2-PadBAT+)") (class "Default")
      (node (ref "ESC2") (pin "BAT+") (pinfunction "BAT+_BAT+") (pintype "passive"))
      (node (ref "FH2") (pin "2") (pinfunction "2_2") (pintype "passive"))
    )
    (net (code "71") (name "Net-(ESC2-PadC)") (class "Default")
      (node (ref "ESC2") (pin "C") (pinfunction "C_C") (pintype "passive"))
      (node (ref "J12") (pin "3") (pintype "passive"))
    )
    (net (code "72") (name "Net-(ESC3-PadA)") (class "Default")
      (node (ref "ESC3") (pin "A") (pinfunction "A_A") (pintype "passive"))
      (node (ref "J15") (pin "1") (pintype "passive"))
    )
    (net (code "73") (name "Net-(ESC3-PadB)") (class "Default")
      (node (ref "ESC3") (pin "B") (pinfunction "B_B") (pintype "passive"))
      (node (ref "J15") (pin "2") (pintype "passive"))
    )
    (net (code "74") (name "Net-(ESC3-PadBAT+)") (class "Default")
      (node (ref "ESC3") (pin "BAT+") (pinfunction "BAT+_BAT+") (pintype "passive"))
      (node (ref "FH3") (pin "2") (pinfunction "2_2") (pintype "passive"))
    )
    (net (code "75") (name "Net-(ESC3-PadC)") (class "Default")
      (node (ref "ESC3") (pin "C") (pinfunction "C_C") (pintype "passive"))
      (node (ref "J15") (pin "3") (pintype "passive"))
    )
    (net (code "76") (name "Net-(ESC4-PadA)") (class "Default")
      (node (ref "ESC4") (pin "A") (pinfunction "A_A") (pintype "passive"))
      (node (ref "J17") (pin "1") (pintype "passive"))
    )
    (net (code "77") (name "Net-(ESC4-PadB)") (class "Default")
      (node (ref "ESC4") (pin "B") (pinfunction "B_B") (pintype "passive"))
      (node (ref "J17") (pin "2") (pintype "passive"))
    )
    (net (code "78") (name "Net-(ESC4-PadBAT+)") (class "Default")
      (node (ref "ESC4") (pin "BAT+") (pinfunction "BAT+_BAT+") (pintype "passive"))
      (node (ref "FH4") (pin "2") (pinfunction "2_2") (pintype "passive"))
    )
    (net (code "79") (name "Net-(ESC4-PadC)") (class "Default")
      (node (ref "ESC4") (pin "C") (pinfunction "C_C") (pintype "passive"))
      (node (ref "J17") (pin "3") (pintype "passive"))
    )
    (net (code "80") (name "Net-(ESC5-PadA)") (class "Default")
      (node (ref "ESC5") (pin "A") (pinfunction "A_A") (pintype "passive"))
      (node (ref "J20") (pin "1") (pintype "passive"))
    )
    (net (code "81") (name "Net-(ESC5-PadB)") (class "Default")
      (node (ref "ESC5") (pin "B") (pinfunction "B_B") (pintype "passive"))
      (node (ref "J20") (pin "2") (pintype "passive"))
    )
    (net (code "82") (name "Net-(ESC5-PadBAT+)") (class "Default")
      (node (ref "ESC5") (pin "BAT+") (pinfunction "BAT+_BAT+") (pintype "passive"))
      (node (ref "FH5") (pin "2") (pinfunction "2_2") (pintype "passive"))
    )
    (net (code "83") (name "Net-(ESC5-PadC)") (class "Default")
      (node (ref "ESC5") (pin "C") (pinfunction "C_C") (pintype "passive"))
      (node (ref "J20") (pin "3") (pintype "passive"))
    )
    (net (code "84") (name "Net-(ESC6-PadA)") (class "Default")
      (node (ref "ESC6") (pin "A") (pinfunction "A_A") (pintype "passive"))
      (node (ref "J21") (pin "1") (pintype "passive"))
    )
    (net (code "85") (name "Net-(ESC6-PadB)") (class "Default")
      (node (ref "ESC6") (pin "B") (pinfunction "B_B") (pintype "passive"))
      (node (ref "J21") (pin "2") (pintype "passive"))
    )
    (net (code "86") (name "Net-(ESC6-PadBAT+)") (class "Default")
      (node (ref "ESC6") (pin "BAT+") (pinfunction "BAT+_BAT+") (pintype "passive"))
      (node (ref "FH6") (pin "2") (pinfunction "2_2") (pintype "passive"))
    )
    (net (code "87") (name "Net-(ESC6-PadC)") (class "Default")
      (node (ref "ESC6") (pin "C") (pinfunction "C_C") (pintype "passive"))
      (node (ref "J21") (pin "3") (pintype "passive"))
    )
    (net (code "88") (name "Net-(ESC7-PadA)") (class "Default")
      (node (ref "ESC7") (pin "A") (pinfunction "A_A") (pintype "passive"))
      (node (ref "J23") (pin "1") (pintype "passive"))
    )
    (net (code "89") (name "Net-(ESC7-PadB)") (class "Default")
      (node (ref "ESC7") (pin "B") (pinfunction "B_B") (pintype "passive"))
      (node (ref "J23") (pin "2") (pintype "passive"))
    )
    (net (code "90") (name "Net-(ESC7-PadBAT+)") (class "Default")
      (node (ref "ESC7") (pin "BAT+") (pinfunction "BAT+_BAT+") (pintype "passive"))
      (node (ref "FH7") (pin "2") (pinfunction "2_2") (pintype "passive"))
    )
    (net (code "91") (name "Net-(ESC7-PadC)") (class "Default")
      (node (ref "ESC7") (pin "C") (pinfunction "C_C") (pintype "passive"))
      (node (ref "J23") (pin "3") (pintype "passive"))
    )
    (net (code "92") (name "Net-(ESC8-PadA)") (class "Default")
      (node (ref "ESC8") (pin "A") (pinfunction "A_A") (pintype "passive"))
      (node (ref "J24") (pin "1") (pintype "passive"))
    )
    (net (code "93") (name "Net-(ESC8-PadB)") (class "Default")
      (node (ref "ESC8") (pin "B") (pinfunction "B_B") (pintype "passive"))
      (node (ref "J24") (pin "2") (pintype "passive"))
    )
    (net (code "94") (name "Net-(ESC8-PadBAT+)") (class "Default")
      (node (ref "ESC8") (pin "BAT+") (pinfunction "BAT+_BAT+") (pintype "passive"))
      (node (ref "FH8") (pin "2") (pinfunction "2_2") (pintype "passive"))
    )
    (net (code "95") (name "Net-(ESC8-PadC)") (class "Default")
      (node (ref "ESC8") (pin "C") (pinfunction "C_C") (pintype "passive"))
      (node (ref "J24") (pin "3") (pintype "passive"))
    )
    (net (code "96") (name "Net-(U1-ADR)") (class "Default")
      (node (ref "R14") (pin "2") (pinfunction "2_2") (pintype "passive"))
      (node (ref "R15") (pin "1") (pinfunction "1_1") (pintype "passive"))
      (node (ref "U1") (pin "7") (pinfunction "ADR_7") (pintype "passive"))
    )
    (net (code "97") (name "VBATT") (class "Default")
      (node (ref "J1") (pin "2") (pintype "passive"))
      (node (ref "J10") (pin "2") (pintype "passive"))
    )
    (net (code "98") (name "VBATT_RELAY") (class "Default")
      (node (ref "FH1") (pin "1") (pinfunction "1_1") (pintype "passive"))
      (node (ref "FH2") (pin "1") (pinfunction "1_1") (pintype "passive"))
      (node (ref "FH3") (pin "1") (pinfunction "1_1") (pintype "passive"))
      (node (ref "FH4") (pin "1") (pinfunction "1_1") (pintype "passive"))
      (node (ref "FH5") (pin "1") (pinfunction "1_1") (pintype "passive"))
      (node (ref "FH6") (pin "1") (pinfunction "1_1") (pintype "passive"))
      (node (ref "FH7") (pin "1") (pinfunction "1_1") (pintype "passive"))
      (node (ref "FH8") (pin "1") (pinfunction "1_1") (pintype "passive"))
    )
    (net (code "99") (name "Valve_1") (class "Default")
      (node (ref "D1") (pin "A") (pinfunction "A_A") (pintype "passive"))
      (node (ref "J2") (pin "2") (pintype "passive"))
    )
    (net (code "100") (name "Valve_2") (class "Default")
      (node (ref "D2") (pin "A") (pinfunction "A_A") (pintype "passive"))
      (node (ref "J3") (pin "2") (pintype "passive"))
    )
    (net (code "101") (name "Valve_3") (class "Default")
      (node (ref "D3") (pin "A") (pinfunction "A_A") (pintype "passive"))
      (node (ref "J4") (pin "2") (pintype "passive"))
    )
    (net (code "102") (name "Valve_4") (class "Default")
      (node (ref "D4") (pin "A") (pinfunction "A_A") (pintype "passive"))
      (node (ref "J5") (pin "2") (pintype "passive"))
    )
    (net (code "103") (name "Valve_5") (class "Default")
      (node (ref "D5") (pin "A") (pinfunction "A_A") (pintype "passive"))
      (node (ref "J6") (pin "2") (pintype "passive"))
    )
    (net (code "104") (name "unconnected-(ESC1-PadNC)") (class "Default")
      (node (ref "ESC1") (pin "NC") (pinfunction "NC_NC") (pintype "passive+no_connect"))
    )
    (net (code "105") (name "unconnected-(ESC2-PadNC)") (class "Default")
      (node (ref "ESC2") (pin "NC") (pinfunction "NC_NC") (pintype "passive+no_connect"))
    )
    (net (code "106") (name "unconnected-(ESC3-PadNC)") (class "Default")
      (node (ref "ESC3") (pin "NC") (pinfunction "NC_NC") (pintype "passive+no_connect"))
    )
    (net (code "107") (name "unconnected-(ESC4-PadNC)") (class "Default")
      (node (ref "ESC4") (pin "NC") (pinfunction "NC_NC") (pintype "passive+no_connect"))
    )
    (net (code "108") (name "unconnected-(ESC5-PadNC)") (class "Default")
      (node (ref "ESC5") (pin "NC") (pinfunction "NC_NC") (pintype "passive+no_connect"))
    )
    (net (code "109") (name "unconnected-(ESC6-PadNC)") (class "Default")
      (node (ref "ESC6") (pin "NC") (pinfunction "NC_NC") (pintype "passive+no_connect"))
    )
    (net (code "110") (name "unconnected-(ESC7-PadNC)") (class "Default")
      (node (ref "ESC7") (pin "NC") (pinfunction "NC_NC") (pintype "passive+no_connect"))
    )
    (net (code "111") (name "unconnected-(ESC8-PadNC)") (class "Default")
      (node (ref "ESC8") (pin "NC") (pinfunction "NC_NC") (pintype "passive+no_connect"))
    )
    (net (code "112") (name "unconnected-(U1-3VO-Pad2)") (class "Default")
      (node (ref "U1") (pin "2") (pinfunction "3VO_2") (pintype "passive+no_connect"))
    )
    (net (code "113") (name "unconnected-(U1-INT-Pad8)") (class "Default")
      (node (ref "U1") (pin "8") (pinfunction "INT_8") (pintype "passive+no_connect"))
    )
    (net (code "114") (name "unconnected-(U1-PS0-Pad10)") (class "Default")
      (node (ref "U1") (pin "10") (pinfunction "PS0_10") (pintype "passive+no_connect"))
    )
    (net (code "115") (name "unconnected-(U1-PS1-Pad9)") (class "Default")
      (node (ref "U1") (pin "9") (pinfunction "PS1_9") (pintype "passive+no_connect"))
    )
    (net (code "116") (name "unconnected-(U1-RST-Pad6)") (class "Default")
      (node (ref "U1") (pin "6") (pinfunction "RST_6") (pintype "power_in+no_connect"))
    )
  )
)
